# Launch_Tower_Power_Interface_Board_v1-3.net
KiCad netlist of a schematic drawn in EAGLE
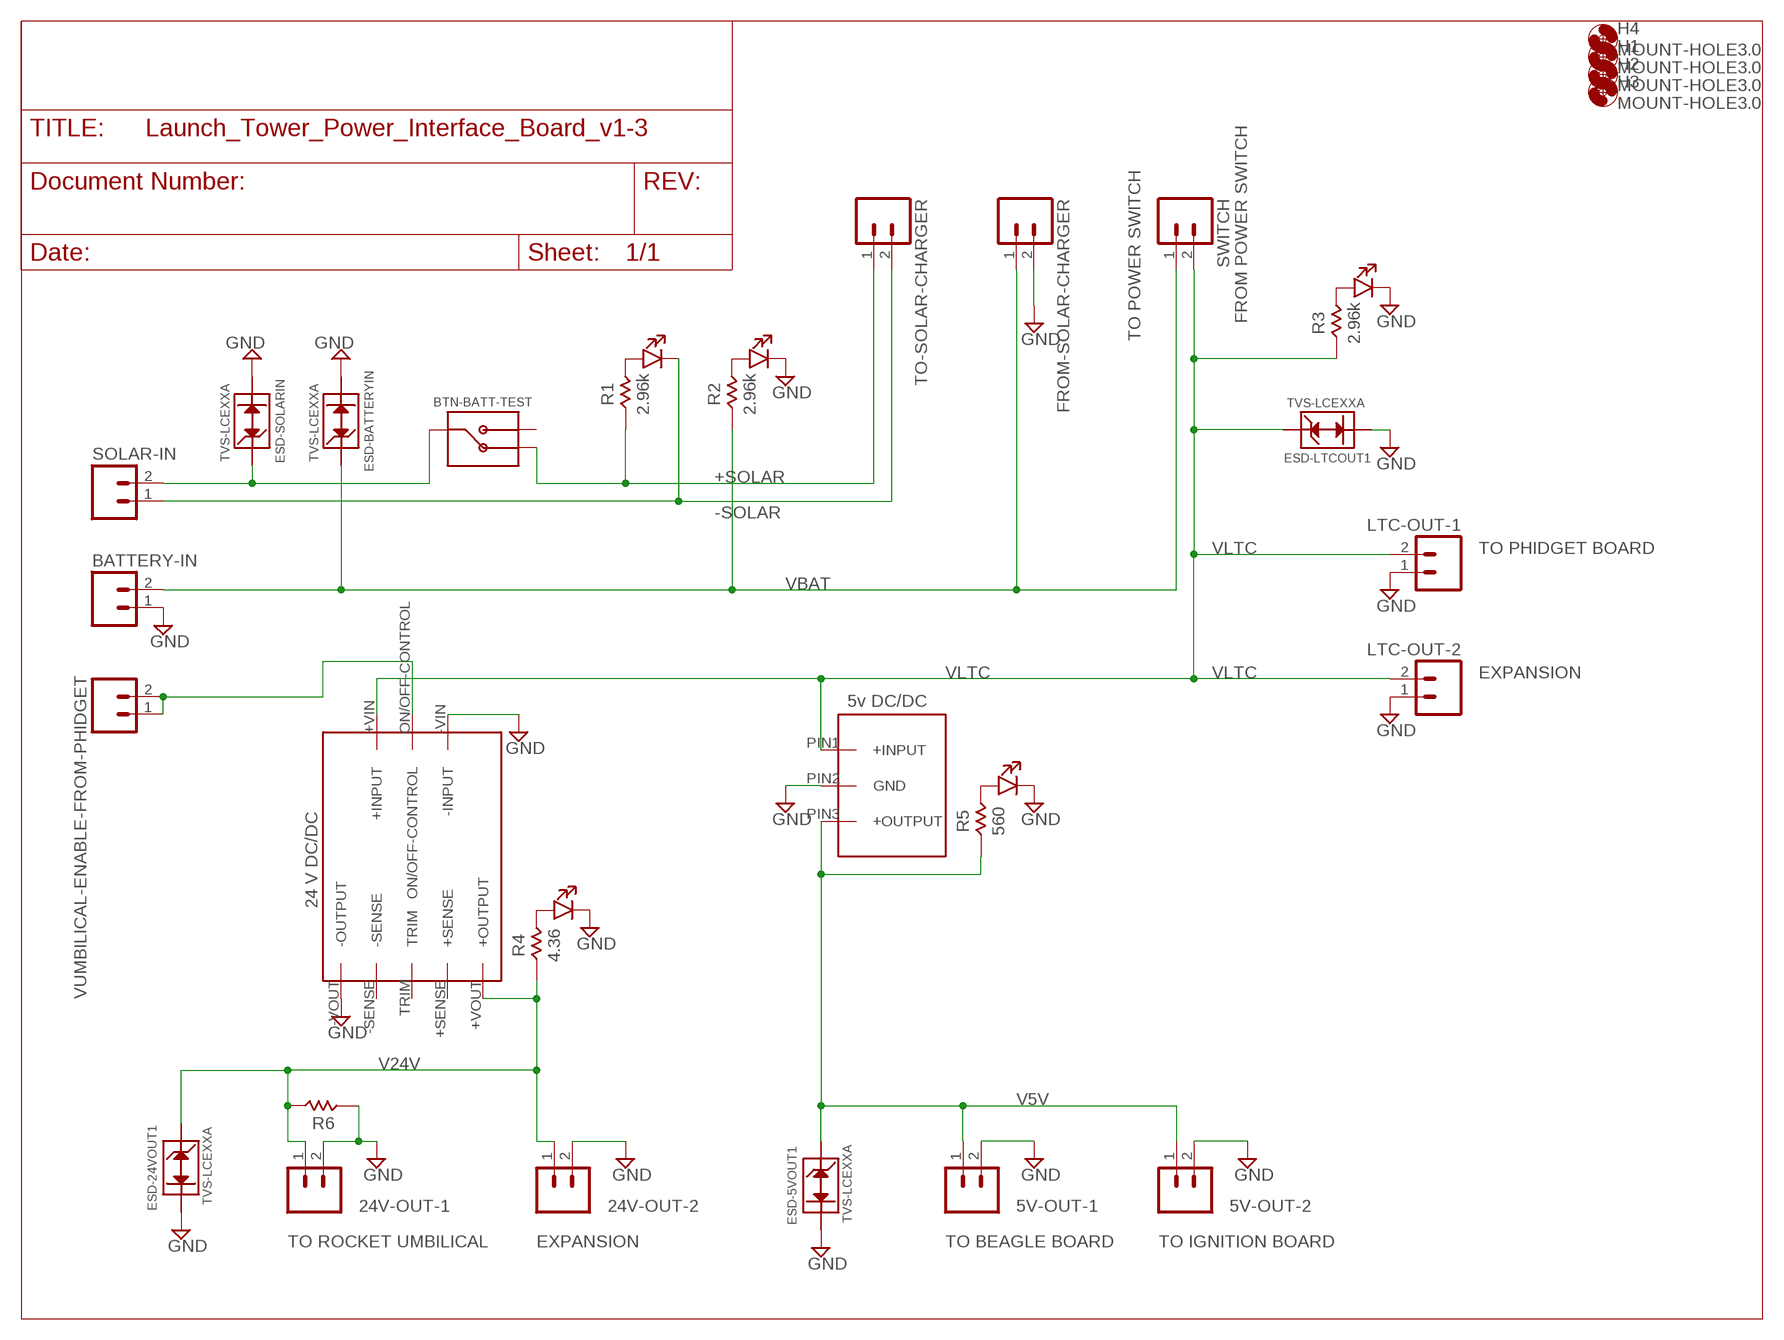
[diagram p0: schematic, sheet 1]

(export (version "E")
  (design (tool "Eeschema 10.0.6"))
  (components
    (comp (ref "5V-OUT-1")
      (value "M025MM")
      (footprint "eagle-import:SCREWTERMINAL-5MM-2")
      (libsource (lib "eagle-import") (part "M025MM"))
    )
    (comp (ref "5V-OUT-2")
      (value "M025MM")
      (footprint "eagle-import:SCREWTERMINAL-5MM-2")
      (libsource (lib "eagle-import") (part "M025MM"))
    )
    (comp (ref "24V-OUT-1")
      (value "M025MM")
      (footprint "eagle-import:SCREWTERMINAL-5MM-2")
      (libsource (lib "eagle-import") (part "M025MM"))
    )
    (comp (ref "24V-OUT-2")
      (value "M025MM")
      (footprint "eagle-import:SCREWTERMINAL-5MM-2")
      (libsource (lib "eagle-import") (part "M025MM"))
    )
    (comp (ref "BATTERY-IN")
      (value "M025MM")
      (footprint "eagle-import:SCREWTERMINAL-5MM-2")
      (libsource (lib "eagle-import") (part "M025MM"))
    )
    (comp (ref "BTN-BATT-TEST")
      (value "BUTTON-107-3006-EVX")
      (footprint "eagle-import:BUTTON-1")
      (libsource (lib "eagle-import") (part "BUTTON-107-3006-EVX"))
    )
    (comp (ref "ESD-5VOUT1")
      (value "TVS-LCEXXA")
      (footprint "eagle-import:D0-201")
      (libsource (lib "eagle-import") (part "TVS-LCEXXA"))
    )
    (comp (ref "ESD-24VOUT1")
      (value "TVS-LCEXXA")
      (footprint "eagle-import:D0-201")
      (libsource (lib "eagle-import") (part "TVS-LCEXXA"))
    )
    (comp (ref "ESD-BATTERYIN")
      (value "TVS-LCEXXA")
      (footprint "eagle-import:D0-201")
      (libsource (lib "eagle-import") (part "TVS-LCEXXA"))
    )
    (comp (ref "ESD-LTCOUT1")
      (value "TVS-LCEXXA")
      (footprint "eagle-import:D0-201")
      (libsource (lib "eagle-import") (part "TVS-LCEXXA"))
    )
    (comp (ref "ESD-SOLARIN")
      (value "TVS-LCEXXA")
      (footprint "eagle-import:D0-201")
      (libsource (lib "eagle-import") (part "TVS-LCEXXA"))
    )
    (comp (ref "FROM-SOLAR-CHARGER")
      (value "M025MM")
      (footprint "eagle-import:SCREWTERMINAL-5MM-2")
      (libsource (lib "eagle-import") (part "M025MM"))
    )
    (comp (ref "H1")
      (value "MOUNT-HOLE3.0")
      (footprint "eagle-import:3,0")
      (libsource (lib "eagle-import") (part "MOUNT-HOLE3.0"))
    )
    (comp (ref "H2")
      (value "MOUNT-HOLE3.0")
      (footprint "eagle-import:3,0")
      (libsource (lib "eagle-import") (part "MOUNT-HOLE3.0"))
    )
    (comp (ref "H3")
      (value "MOUNT-HOLE3.0")
      (footprint "eagle-import:3,0")
      (libsource (lib "eagle-import") (part "MOUNT-HOLE3.0"))
    )
    (comp (ref "H4")
      (value "MOUNT-HOLE3.0")
      (footprint "eagle-import:3,0")
      (libsource (lib "eagle-import") (part "MOUNT-HOLE3.0"))
    )
    (comp (ref "LED-5V-DC/DC")
      (value "LED-550-XX04")
      (footprint "eagle-import:LED-550")
      (libsource (lib "eagle-import") (part "LED-550-XX04"))
    )
    (comp (ref "LED-24V-DC/DC")
      (value "LED-550-XX04")
      (footprint "eagle-import:LED-550")
      (libsource (lib "eagle-import") (part "LED-550-XX04"))
    )
    (comp (ref "LED-BATTERY-IN")
      (value "LED-550-XX04")
      (footprint "eagle-import:LED-550")
      (libsource (lib "eagle-import") (part "LED-550-XX04"))
    )
    (comp (ref "LED-SOLAR-IN")
      (value "LED-550-XX04")
      (footprint "eagle-import:LED-550")
      (libsource (lib "eagle-import") (part "LED-550-XX04"))
    )
    (comp (ref "LED-SWITCH-IN")
      (value "LED-550-XX04")
      (footprint "eagle-import:LED-550")
      (libsource (lib "eagle-import") (part "LED-550-XX04"))
    )
    (comp (ref "LTC-OUT-1")
      (value "M025MM")
      (footprint "eagle-import:SCREWTERMINAL-5MM-2")
      (libsource (lib "eagle-import") (part "M025MM"))
    )
    (comp (ref "LTC-OUT-2")
      (value "M025MM")
      (footprint "eagle-import:SCREWTERMINAL-5MM-2")
      (libsource (lib "eagle-import") (part "M025MM"))
    )
    (comp (ref "R1")
      (value "2.96k")
      (footprint "eagle-import:0805")
      (libsource (lib "eagle-import") (part "RESISTOR-0805"))
    )
    (comp (ref "R2")
      (value "2.96k")
      (footprint "eagle-import:0805")
      (libsource (lib "eagle-import") (part "RESISTOR-0805"))
    )
    (comp (ref "R3")
      (value "2.96k")
      (footprint "eagle-import:0805")
      (libsource (lib "eagle-import") (part "RESISTOR-0805"))
    )
    (comp (ref "R4")
      (value "4.36")
      (footprint "eagle-import:0805")
      (libsource (lib "eagle-import") (part "RESISTOR-0805"))
    )
    (comp (ref "R5")
      (value "560")
      (footprint "eagle-import:0805")
      (libsource (lib "eagle-import") (part "RESISTOR-0805"))
    )
    (comp (ref "R6")
      (value "RESISTOR-0805")
      (footprint "eagle-import:0805")
      (libsource (lib "eagle-import") (part "RESISTOR-0805"))
    )
    (comp (ref "SOLAR-IN")
      (value "M025MM")
      (footprint "eagle-import:SCREWTERMINAL-5MM-2")
      (libsource (lib "eagle-import") (part "M025MM"))
    )
    (comp (ref "SWITCH")
      (value "M025MM")
      (footprint "eagle-import:SCREWTERMINAL-5MM-2")
      (libsource (lib "eagle-import") (part "M025MM"))
    )
    (comp (ref "TO-SOLAR-CHARGER")
      (value "M025MM")
      (footprint "eagle-import:SCREWTERMINAL-5MM-2")
      (libsource (lib "eagle-import") (part "M025MM"))
    )
    (comp (ref "U$1")
      (value "DC/DC_CONV_24V")
      (footprint "eagle-import:UWE")
      (libsource (lib "eagle-import") (part "DC/DC_CONV_24V"))
    )
    (comp (ref "U$2")
      (value "DC/DC_CONV_5V")
      (footprint "eagle-import:OKI-SIP")
      (libsource (lib "eagle-import") (part "DC/DC_CONV_5V"))
    )
    (comp (ref "VUMBILICAL-ENABLE-FROM-PHIDGET")
      (value "M023.5MM")
      (footprint "eagle-import:SCREWTERMINAL-3.5MM-2")
      (libsource (lib "eagle-import") (part "SparkFun-Connectors_M023.5MM"))
    )
  )
  (nets
    (net (code "1") (name "/+SOLAR") (class "Default")
      (node (ref "BTN-BATT-TEST") (pin "NC") (pinfunction "NC_NC") (pintype "bidirectional"))
      (node (ref "R1") (pin "ANODE") (pinfunction "ANODE_ANODE") (pintype "bidirectional"))
      (node (ref "TO-SOLAR-CHARGER") (pin "1") (pinfunction "1_1") (pintype "passive"))
    )
    (net (code "2") (name "/-SOLAR") (class "Default")
      (node (ref "LED-SOLAR-IN") (pin "CATHODE") (pinfunction "CATHODE_CATHODE") (pintype "bidirectional"))
      (node (ref "SOLAR-IN") (pin "1") (pinfunction "1_1") (pintype "passive"))
      (node (ref "TO-SOLAR-CHARGER") (pin "2") (pinfunction "2_2") (pintype "passive"))
    )
    (net (code "3") (name "/V5V") (class "Default")
      (node (ref "5V-OUT-1") (pin "1") (pinfunction "1_1") (pintype "passive"))
      (node (ref "5V-OUT-2") (pin "1") (pinfunction "1_1") (pintype "passive"))
      (node (ref "ESD-5VOUT1") (pin "ANODE") (pinfunction "ANODE_ANODE") (pintype "bidirectional"))
      (node (ref "R5") (pin "ANODE") (pinfunction "ANODE_ANODE") (pintype "bidirectional"))
      (node (ref "U$2") (pin "PIN3") (pinfunction "+OUTPUT_PIN3") (pintype "bidirectional"))
    )
    (net (code "4") (name "/V24V") (class "Default")
      (node (ref "24V-OUT-1") (pin "1") (pinfunction "1_1") (pintype "passive"))
      (node (ref "24V-OUT-2") (pin "1") (pinfunction "1_1") (pintype "passive"))
      (node (ref "ESD-24VOUT1") (pin "ANODE") (pinfunction "ANODE_ANODE") (pintype "bidirectional"))
      (node (ref "R4") (pin "ANODE") (pinfunction "ANODE_ANODE") (pintype "bidirectional"))
      (node (ref "R6") (pin "CATHODE") (pinfunction "CATHODE_CATHODE") (pintype "bidirectional"))
      (node (ref "U$1") (pin "+VOUT") (pinfunction "+OUTPUT_+VOUT") (pintype "bidirectional"))
    )
    (net (code "5") (name "/VBAT") (class "Default")
      (node (ref "BATTERY-IN") (pin "2") (pinfunction "2_2") (pintype "passive"))
      (node (ref "ESD-BATTERYIN") (pin "ANODE") (pinfunction "ANODE_ANODE") (pintype "bidirectional"))
      (node (ref "FROM-SOLAR-CHARGER") (pin "1") (pinfunction "1_1") (pintype "passive"))
      (node (ref "R2") (pin "ANODE") (pinfunction "ANODE_ANODE") (pintype "bidirectional"))
      (node (ref "SWITCH") (pin "1") (pinfunction "1_1") (pintype "passive"))
    )
    (net (code "6") (name "/VLTC") (class "Default")
      (node (ref "ESD-LTCOUT1") (pin "ANODE") (pinfunction "ANODE_ANODE") (pintype "bidirectional"))
      (node (ref "LTC-OUT-1") (pin "2") (pinfunction "2_2") (pintype "passive"))
      (node (ref "LTC-OUT-2") (pin "2") (pinfunction "2_2") (pintype "passive"))
      (node (ref "R3") (pin "ANODE") (pinfunction "ANODE_ANODE") (pintype "bidirectional"))
      (node (ref "SWITCH") (pin "2") (pinfunction "2_2") (pintype "passive"))
      (node (ref "U$1") (pin "+VIN") (pinfunction "+INPUT_+VIN") (pintype "bidirectional"))
      (node (ref "U$2") (pin "PIN1") (pinfunction "+INPUT_PIN1") (pintype "bidirectional"))
    )
    (net (code "7") (name "GND") (class "Default")
      (node (ref "24V-OUT-1") (pin "2") (pinfunction "2_2") (pintype "passive"))
      (node (ref "24V-OUT-2") (pin "2") (pinfunction "2_2") (pintype "passive"))
      (node (ref "5V-OUT-1") (pin "2") (pinfunction "2_2") (pintype "passive"))
      (node (ref "5V-OUT-2") (pin "2") (pinfunction "2_2") (pintype "passive"))
      (node (ref "BATTERY-IN") (pin "1") (pinfunction "1_1") (pintype "passive"))
      (node (ref "ESD-24VOUT1") (pin "CATHODE") (pinfunction "CATHODE_CATHODE") (pintype "bidirectional"))
      (node (ref "ESD-5VOUT1") (pin "CATHODE") (pinfunction "CATHODE_CATHODE") (pintype "bidirectional"))
      (node (ref "ESD-BATTERYIN") (pin "CATHODE") (pinfunction "CATHODE_CATHODE") (pintype "bidirectional"))
      (node (ref "ESD-LTCOUT1") (pin "CATHODE") (pinfunction "CATHODE_CATHODE") (pintype "bidirectional"))
      (node (ref "ESD-SOLARIN") (pin "CATHODE") (pinfunction "CATHODE_CATHODE") (pintype "bidirectional"))
      (node (ref "FROM-SOLAR-CHARGER") (pin "2") (pinfunction "2_2") (pintype "passive"))
      (node (ref "LED-24V-DC/DC") (pin "CATHODE") (pinfunction "CATHODE_CATHODE") (pintype "bidirectional"))
      (node (ref "LED-5V-DC/DC") (pin "CATHODE") (pinfunction "CATHODE_CATHODE") (pintype "bidirectional"))
      (node (ref "LED-BATTERY-IN") (pin "CATHODE") (pinfunction "CATHODE_CATHODE") (pintype "bidirectional"))
      (node (ref "LED-SWITCH-IN") (pin "CATHODE") (pinfunction "CATHODE_CATHODE") (pintype "bidirectional"))
      (node (ref "LTC-OUT-1") (pin "1") (pinfunction "1_1") (pintype "passive"))
      (node (ref "LTC-OUT-2") (pin "1") (pinfunction "1_1") (pintype "passive"))
      (node (ref "R6") (pin "ANODE") (pinfunction "ANODE_ANODE") (pintype "bidirectional"))
      (node (ref "U$1") (pin "-VIN") (pinfunction "-INPUT_-VIN") (pintype "bidirectional"))
      (node (ref "U$1") (pin "-VOUT") (pinfunction "-OUTPUT_-VOUT") (pintype "bidirectional"))
      (node (ref "U$2") (pin "PIN2") (pinfunction "GND_PIN2") (pintype "bidirectional"))
    )
    (net (code "8") (name "Net-(BTN-BATT-TEST-PadCOMMON)") (class "Default")
      (node (ref "BTN-BATT-TEST") (pin "COMMON") (pinfunction "COMMON_COMMON") (pintype "bidirectional"))
      (node (ref "ESD-SOLARIN") (pin "ANODE") (pinfunction "ANODE_ANODE") (pintype "bidirectional"))
      (node (ref "SOLAR-IN") (pin "2") (pinfunction "2_2") (pintype "passive"))
    )
    (net (code "9") (name "Net-(LED-5V-DC/DC-PadANODE)") (class "Default")
      (node (ref "LED-5V-DC/DC") (pin "ANODE") (pinfunction "ANODE_ANODE") (pintype "bidirectional"))
      (node (ref "R5") (pin "CATHODE") (pinfunction "CATHODE_CATHODE") (pintype "bidirectional"))
    )
    (net (code "10") (name "Net-(LED-24V-DC/DC-PadANODE)") (class "Default")
      (node (ref "LED-24V-DC/DC") (pin "ANODE") (pinfunction "ANODE_ANODE") (pintype "bidirectional"))
      (node (ref "R4") (pin "CATHODE") (pinfunction "CATHODE_CATHODE") (pintype "bidirectional"))
    )
    (net (code "11") (name "Net-(LED-BATTERY-IN-PadANODE)") (class "Default")
      (node (ref "LED-BATTERY-IN") (pin "ANODE") (pinfunction "ANODE_ANODE") (pintype "bidirectional"))
      (node (ref "R2") (pin "CATHODE") (pinfunction "CATHODE_CATHODE") (pintype "bidirectional"))
    )
    (net (code "12") (name "Net-(LED-SOLAR-IN-PadANODE)") (class "Default")
      (node (ref "LED-SOLAR-IN") (pin "ANODE") (pinfunction "ANODE_ANODE") (pintype "bidirectional"))
      (node (ref "R1") (pin "CATHODE") (pinfunction "CATHODE_CATHODE") (pintype "bidirectional"))
    )
    (net (code "13") (name "Net-(LED-SWITCH-IN-PadANODE)") (class "Default")
      (node (ref "LED-SWITCH-IN") (pin "ANODE") (pinfunction "ANODE_ANODE") (pintype "bidirectional"))
      (node (ref "R3") (pin "CATHODE") (pinfunction "CATHODE_CATHODE") (pintype "bidirectional"))
    )
    (net (code "14") (name "Net-(U$1-PadON{slash}OFF-CONTROL)") (class "Default")
      (node (ref "U$1") (pin "ON/OFF-CONTROL") (pinfunction "ON/OFF-CONTROL_ON/OFF-CONTROL") (pintype "bidirectional"))
      (node (ref "VUMBILICAL-ENABLE-FROM-PHIDGET") (pin "1") (pinfunction "1_1") (pintype "passive"))
      (node (ref "VUMBILICAL-ENABLE-FROM-PHIDGET") (pin "2") (pinfunction "2_2") (pintype "passive"))
    )
    (net (code "15") (name "unconnected-(BTN-BATT-TEST-PadNO)") (class "Default")
      (node (ref "BTN-BATT-TEST") (pin "NO") (pinfunction "NO_NO") (pintype "bidirectional"))
    )
    (net (code "16") (name "unconnected-(U$1-Pad+SENSE)") (class "Default")
      (node (ref "U$1") (pin "+SENSE") (pinfunction "+SENSE_+SENSE") (pintype "bidirectional"))
    )
    (net (code "17") (name "unconnected-(U$1-Pad-SENSE)") (class "Default")
      (node (ref "U$1") (pin "-SENSE") (pinfunction "-SENSE_-SENSE") (pintype "bidirectional"))
    )
    (net (code "18") (name "unconnected-(U$1-PadTRIM)") (class "Default")
      (node (ref "U$1") (pin "TRIM") (pinfunction "TRIM_TRIM") (pintype "bidirectional"))
    )
  )
)
